# ct_interface.net
KiCad netlist of a schematic drawn in Altium Designer
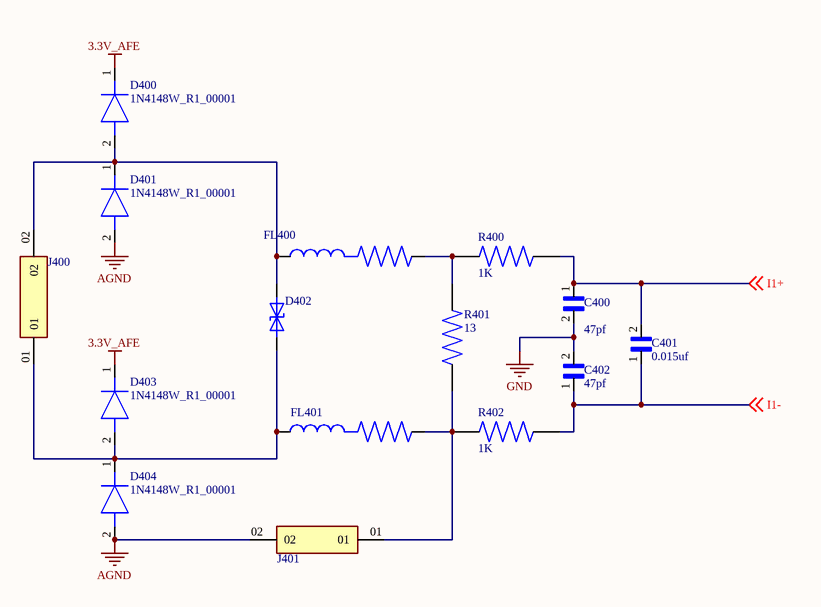
[diagram p0: ct_interface.SchDoc]

(export (version "E")
  (design (tool "Eeschema 10.0.6"))
  (components
    (comp (ref "C400")
      (value "47pf")
      (footprint "CAPC1608X90")
      (description "CAP CER 47PF 50V C0G/NPO 0603")
      (fields (field (name "MP") "CC0603JRNPO9BN470") (field (name "MF") "{'manufacturer': u'Yageo'}"))
      (libsource (lib "SnapEDA_Library") (part "CC0603JRNPO9BN470"))
    )
    (comp (ref "C401")
      (value "0.015uf")
      (footprint "CAPC1608X87N")
      (description "VJ_W1BC")
      (fields
        (field (name "MP") "VJ0603Y153KXAPW1BC")
        (field (name "MF") "{'manufacturer': u'Vishay Vitramon'}")
      )
      (libsource (lib "SnapEDA_Library") (part "VJ0603Y153KXAPW1BC"))
    )
    (comp (ref "C402")
      (value "47pf")
      (footprint "CAPC1608X90")
      (description "CAP CER 47PF 50V C0G/NPO 0603")
      (fields (field (name "MP") "CC0603JRNPO9BN470") (field (name "MF") "{'manufacturer': u'Yageo'}"))
      (libsource (lib "") (part "CC0603JRNPO9BN470_1"))
    )
    (comp (ref "D400")
      (value "1N4148W_R1_00001")
      (footprint "SOD3816X135N")
      (description "Diode")
      (fields (field (name "MOUSER PART NUMBER") "241-1N4148W_R1_00001"))
      (libsource (lib "chargebot_digital_2g") (part "1N4148W_R1_00001"))
    )
    (comp (ref "D401")
      (value "1N4148W_R1_00001")
      (footprint "SOD3816X135N")
      (description "Diode")
      (fields (field (name "MOUSER PART NUMBER") "241-1N4148W_R1_00001"))
      (libsource (lib "*") (part "1N4148W_R1_00001"))
    )
    (comp (ref "D402")
      (value "SMAJ5.0CA-13-F")
      (footprint "DIOM5126X229N")
      (description "9.2V Clamp 43.5A Ipp Tvs Diode Surface Mount SMA (DO-214AC)")
      (fields (field (name "MF") "{'manufacturer': u'Diodes Inc.'}"))
      (libsource (lib "SnapEDA_Library") (part "SMAJ5.0CA-13-F"))
    )
    (comp (ref "D403")
      (value "1N4148W_R1_00001")
      (footprint "SOD3816X135N")
      (description "Diode")
      (fields (field (name "MOUSER PART NUMBER") "241-1N4148W_R1_00001"))
      (libsource (lib "*") (part "1N4148W_R1_00001"))
    )
    (comp (ref "D404")
      (value "1N4148W_R1_00001")
      (footprint "SOD3816X135N")
      (description "Diode")
      (fields (field (name "MOUSER PART NUMBER") "241-1N4148W_R1_00001"))
      (libsource (lib "*") (part "1N4148W_R1_00001"))
    )
    (comp (ref "FL400")
      (value "BLM21BD121SN1D")
      (footprint "BEADC2012X105N")
      (description "Ferrite: bead; 120Î©; Mounting: SMD; 200mA; -55Ã·125Â°C")
      (fields (field (name "MF") "{'manufacturer': u'Murata Electronics'}"))
      (libsource (lib "SnapEDA_Library") (part "BLM21BD121SN1D"))
    )
    (comp (ref "FL401")
      (value "BLM21BD121SN1D")
      (footprint "BEADC2012X105N")
      (description "Ferrite: bead; 120Î©; Mounting: SMD; 200mA; -55Ã·125Â°C")
      (fields (field (name "MF") "{'manufacturer': u'Murata Electronics'}"))
      (libsource (lib "SnapEDA_Library") (part "BLM21BD121SN1D"))
    )
    (comp (ref "J400")
      (value "MTMM-101-10-G-D-135")
      (footprint "SAMTEC_MTMM-101-10-G-D-135")
      (fields (field (name "MF") "{'manufacturer': u'Samtec'}"))
      (libsource (lib "*") (part "MTMM-101-10-G-D-135"))
    )
    (comp (ref "J401")
      (value "MTMM-101-10-G-D-135")
      (footprint "SAMTEC_MTMM-101-10-G-D-135")
      (fields (field (name "MF") "{'manufacturer': u'Samtec'}"))
      (libsource (lib "") (part "MTMM-101-10-G-D-135_1"))
    )
    (comp (ref "R400")
      (value "1K")
      (footprint "RESC1608X55 - duplicate")
      (description "Resistor; Thick Film; Res 1 Kilohms; Pwr-Rtg 0.1 W; Tol 1%; SMT; 0603")
      (fields (field (name "MP") "CR0603-FX-1001ELF") (field (name "MF") "{'manufacturer': u'Bourns'}"))
      (libsource (lib "SnapEDA_Library") (part "CR0603-FX-1001ELF"))
    )
    (comp (ref "R401")
      (value "13")
      (footprint "RESC1608X55N - duplicate")
      (description "Resistor; Thick Film; Res 1 Kilohms; Pwr-Rtg 0.1 W; Tol 1%; SMT; 0603")
      (fields (field (name "MP") "CR0603-FX-1001ELF") (field (name "MF") "{'manufacturer': u'Bourns'}"))
      (libsource (lib "SnapEDA_Library") (part "CR0603-FX-1001ELF"))
    )
    (comp (ref "R402")
      (value "1K")
      (footprint "RESC1608X55N - duplicate")
      (description "Resistor; Thick Film; Res 1 Kilohms; Pwr-Rtg 0.1 W; Tol 1%; SMT; 0603")
      (fields (field (name "MP") "CR0603-FX-1001ELF") (field (name "MF") "{'manufacturer': u'Bourns'}"))
      (libsource (lib "SnapEDA_Library") (part "CR0603-FX-1001ELF"))
    )
  )
  (nets
    (net (code "1") (name "3.3V_AFE") (class "Default")
      (node (ref "D400") (pin "1") (pinfunction "K_1") (pintype "passive"))
      (node (ref "D403") (pin "1") (pinfunction "K_1") (pintype "passive"))
    )
    (net (code "2") (name "AGND") (class "Default")
      (node (ref "D401") (pin "2") (pinfunction "A_2") (pintype "passive"))
      (node (ref "D404") (pin "2") (pinfunction "A_2") (pintype "passive"))
      (node (ref "J401") (pin "02") (pinfunction "02_02") (pintype "passive"))
    )
    (net (code "3") (name "GND") (class "Default")
      (node (ref "C400") (pin "2") (pinfunction "2_2") (pintype "passive"))
      (node (ref "C402") (pin "2") (pinfunction "2_2") (pintype "passive"))
    )
    (net (code "4") (name "I1+") (class "Default")
      (node (ref "C400") (pin "1") (pinfunction "1_1") (pintype "passive"))
      (node (ref "C401") (pin "2") (pinfunction "2_2") (pintype "passive"))
      (node (ref "R400") (pin "1") (pinfunction "1_1") (pintype "passive"))
    )
    (net (code "5") (name "I1-") (class "Default")
      (node (ref "C401") (pin "1") (pinfunction "1_1") (pintype "passive"))
      (node (ref "C402") (pin "1") (pinfunction "1_1") (pintype "passive"))
      (node (ref "R402") (pin "1") (pinfunction "1_1") (pintype "passive"))
    )
    (net (code "6") (name "Net-(D400-A)") (class "Default")
      (node (ref "D400") (pin "2") (pinfunction "A_2") (pintype "passive"))
      (node (ref "D401") (pin "1") (pinfunction "K_1") (pintype "passive"))
      (node (ref "D402") (pin "1") (pinfunction "1_1") (pintype "passive"))
      (node (ref "FL400") (pin "1") (pinfunction "1_1") (pintype "passive"))
      (node (ref "J400") (pin "02") (pinfunction "02_02") (pintype "passive"))
    )
    (net (code "7") (name "Net-(D403-A)") (class "Default")
      (node (ref "D402") (pin "2") (pinfunction "2_2") (pintype "passive"))
      (node (ref "D403") (pin "2") (pinfunction "A_2") (pintype "passive"))
      (node (ref "D404") (pin "1") (pinfunction "K_1") (pintype "passive"))
      (node (ref "FL401") (pin "1") (pinfunction "1_1") (pintype "passive"))
      (node (ref "J400") (pin "01") (pinfunction "01_01") (pintype "passive"))
    )
    (net (code "8") (name "Net-(FL400-Pad2)") (class "Default")
      (node (ref "FL400") (pin "2") (pinfunction "2_2") (pintype "passive"))
      (node (ref "R400") (pin "2") (pinfunction "2_2") (pintype "passive"))
      (node (ref "R401") (pin "2") (pinfunction "2_2") (pintype "passive"))
    )
    (net (code "9") (name "Net-(FL401-Pad2)") (class "Default")
      (node (ref "FL401") (pin "2") (pinfunction "2_2") (pintype "passive"))
      (node (ref "J401") (pin "01") (pinfunction "01_01") (pintype "passive"))
      (node (ref "R401") (pin "1") (pinfunction "1_1") (pintype "passive"))
      (node (ref "R402") (pin "2") (pinfunction "2_2") (pintype "passive"))
    )
  )
)
